# 2Reg.net
KiCad netlist of a schematic drawn in Altium Designer
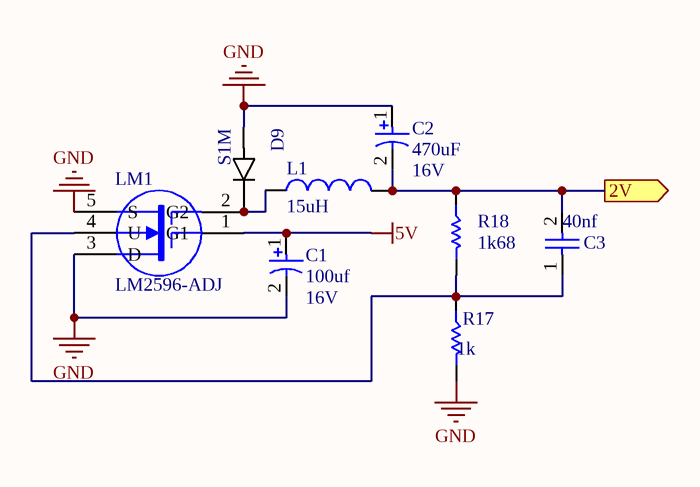
[diagram p0: 2Reg.SchDoc]

(export (version "E")
  (design (tool "Eeschema 10.0.6"))
  (components
    (comp (ref "C1")
      (value "100uf")
      (footprint "RB5-10.5")
      (fields (field (name "ALTIUM_UNNAMED_8") "16V"))
      (libsource (lib "3D LIB") (part "CAP"))
    )
    (comp (ref "C2")
      (value "470uF")
      (footprint "RB5-10.5")
      (fields (field (name "ALTIUM_UNNAMED_8") "16V"))
      (libsource (lib "3D LIB") (part "CAP"))
    )
    (comp (ref "C3") (value "40nf") (footprint "6-0805_L") (libsource (lib "3D LIB") (part "CAP NON")))
    (comp (ref "D9")
      (value "S1M")
      (footprint "*DIOM5227X270N_S1M(Primary)")
      (description "S1 Series 1000 V 1 A 1 uA Surface Mount General Purpose Rectifier - DO-214AC")
      (fields (field (name "MF") "ON Semiconductor"))
      (libsource (lib "S1M") (part "S1M"))
    )
    (comp (ref "L1")
      (value "15uH")
      (footprint "IND_SMD-13.0mm")
      (description "Inductor")
      (libsource (lib "3D LIB") (part "Inductor"))
    )
    (comp (ref "LM1")
      (value "LM2596-ADJ")
      (footprint "T05A")
      (description "Two-Gate, N-Channel MOSFET, Externally Terminated Substrate")
      (fields (field (name "PUBLISHER") "Altium Limited"))
      (libsource (lib "Miscellaneous Devices") (part "MOSFET-N3"))
    )
    (comp (ref "R17") (value "1k") (footprint "6-0805_L") (libsource (lib "3D LIB") (part "RESISTOR")))
    (comp (ref "R18") (value "1k68") (footprint "6-0805_L") (libsource (lib "3D LIB") (part "RESISTOR")))
  )
  (nets
    (net (code "1") (name "/2V") (class "Default")
      (node (ref "C2") (pin "2") (pinfunction "2_2") (pintype "passive"))
      (node (ref "C3") (pin "2") (pinfunction "2_2") (pintype "passive"))
      (node (ref "L1") (pin "2") (pinfunction "2_2") (pintype "passive"))
      (node (ref "R18") (pin "1") (pinfunction "1_1") (pintype "passive"))
    )
    (net (code "2") (name "5V") (class "Default")
      (node (ref "C1") (pin "1") (pinfunction "1_1") (pintype "passive"))
      (node (ref "LM1") (pin "1") (pinfunction "G1_1") (pintype "passive"))
    )
    (net (code "3") (name "GND") (class "Default")
      (node (ref "C1") (pin "2") (pinfunction "2_2") (pintype "passive"))
      (node (ref "C2") (pin "1") (pinfunction "1_1") (pintype "passive"))
      (node (ref "D9") (pin "A") (pinfunction "A_A") (pintype "passive"))
      (node (ref "LM1") (pin "3") (pinfunction "D_3") (pintype "passive"))
      (node (ref "LM1") (pin "5") (pinfunction "S_5") (pintype "passive"))
      (node (ref "R17") (pin "2") (pinfunction "2_2") (pintype "passive"))
    )
    (net (code "4") (name "Net-(D9-K)") (class "Default")
      (node (ref "D9") (pin "C") (pinfunction "K_C") (pintype "passive"))
      (node (ref "L1") (pin "1") (pinfunction "1_1") (pintype "passive"))
      (node (ref "LM1") (pin "2") (pinfunction "G2_2") (pintype "passive"))
    )
    (net (code "5") (name "Net-(LM1-U)") (class "Default")
      (node (ref "C3") (pin "1") (pinfunction "1_1") (pintype "passive"))
      (node (ref "LM1") (pin "4") (pinfunction "U_4") (pintype "passive"))
      (node (ref "R17") (pin "1") (pinfunction "1_1") (pintype "passive"))
      (node (ref "R18") (pin "2") (pinfunction "2_2") (pintype "passive"))
    )
  )
)
